# IIoT_Schematic.net
KiCad netlist of a schematic drawn in EAGLE
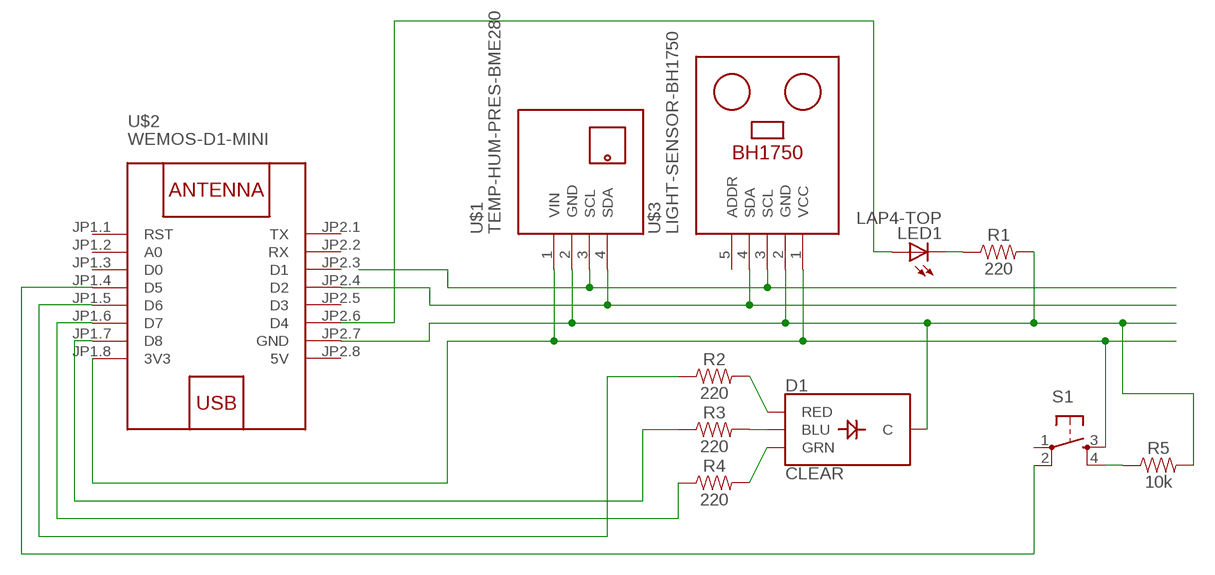
[diagram p0: schematic, sheet 1]

(export (version "E")
  (design (tool "Eeschema 10.0.6"))
  (components
    (comp (ref "D1")
      (value "CLEAR")
      (footprint "eagle-import:LED-RGB-THRU")
      (libsource (lib "eagle-import") (part "LED-RGB-CCCLEAR"))
    )
    (comp (ref "LED1")
      (value "LAP4-TOP")
      (footprint "eagle-import:P47F-TOP")
      (libsource (lib "eagle-import") (part "P4-TOPLA"))
    )
    (comp (ref "R1")
      (value "220")
      (footprint "eagle-import:0603")
      (libsource (lib "eagle-import") (part "220OHM-0603-1/10W-1%"))
    )
    (comp (ref "R2")
      (value "220")
      (footprint "eagle-import:0603")
      (libsource (lib "eagle-import") (part "220OHM-0603-1/10W-1%"))
    )
    (comp (ref "R3")
      (value "220")
      (footprint "eagle-import:0603")
      (libsource (lib "eagle-import") (part "220OHM-0603-1/10W-1%"))
    )
    (comp (ref "R4")
      (value "220")
      (footprint "eagle-import:0603")
      (libsource (lib "eagle-import") (part "220OHM-0603-1/10W-1%"))
    )
    (comp (ref "R5")
      (value "10k")
      (footprint "eagle-import:AXIAL-0.3")
      (libsource (lib "eagle-import") (part "10KOHM-HORIZ-1/4W-1%"))
    )
    (comp (ref "S1")
      (value "TAC_SWITCHPTH")
      (footprint "eagle-import:TACTILE-PTH")
      (libsource (lib "eagle-import") (part "TAC_SWITCHPTH"))
    )
    (comp (ref "U$1")
      (value "TEMP-HUM-PRES-BME280")
      (footprint "eagle-import:TEMP-HUM-PRES-BME280")
      (libsource (lib "eagle-import") (part "TEMP-HUM-PRES-BME280"))
    )
    (comp (ref "U$2")
      (value "WEMOS-D1-MINI")
      (footprint "eagle-import:WEMOS-D1-MINI")
      (libsource (lib "eagle-import") (part "WEMOS-D1-MINI"))
    )
    (comp (ref "U$3")
      (value "LIGHT-SENSOR-BH1750")
      (footprint "eagle-import:LIGHT-SENSOR-BH1750")
      (libsource (lib "eagle-import") (part "LIGHT-SENSOR-BH1750"))
    )
  )
  (nets
    (net (code "1") (name "/5V") (class "Default")
      (node (ref "U$2") (pin "JP2.8") (pinfunction "5V_JP2.8") (pintype "power_in"))
    )
    (net (code "2") (name "Net-(D1-BLU)") (class "Default")
      (node (ref "D1") (pin "4") (pinfunction "BLU_4") (pintype "bidirectional"))
      (node (ref "R3") (pin "2") (pinfunction "2_2") (pintype "passive"))
    )
    (net (code "3") (name "Net-(D1-C)") (class "Default")
      (node (ref "D1") (pin "2") (pinfunction "C_2") (pintype "bidirectional"))
      (node (ref "R1") (pin "2") (pinfunction "2_2") (pintype "passive"))
      (node (ref "R5") (pin "P$2") (pinfunction "2_P$2") (pintype "passive"))
      (node (ref "U$1") (pin "2") (pinfunction "GND_2") (pintype "power_in"))
      (node (ref "U$2") (pin "JP2.7") (pinfunction "GND_JP2.7") (pintype "power_in"))
      (node (ref "U$3") (pin "2") (pinfunction "GND_2") (pintype "power_in"))
    )
    (net (code "4") (name "Net-(D1-GRN)") (class "Default")
      (node (ref "D1") (pin "3") (pinfunction "GRN_3") (pintype "bidirectional"))
      (node (ref "R4") (pin "2") (pinfunction "2_2") (pintype "passive"))
    )
    (net (code "5") (name "Net-(D1-RED)") (class "Default")
      (node (ref "D1") (pin "1") (pinfunction "RED_1") (pintype "bidirectional"))
      (node (ref "R2") (pin "2") (pinfunction "2_2") (pintype "passive"))
    )
    (net (code "6") (name "Net-(LED1-PadC)") (class "Default")
      (node (ref "LED1") (pin "C") (pinfunction "C_C") (pintype "passive"))
      (node (ref "R1") (pin "1") (pinfunction "1_1") (pintype "passive"))
    )
    (net (code "7") (name "Net-(R5-1)") (class "Default")
      (node (ref "R5") (pin "P$1") (pinfunction "1_P$1") (pintype "passive"))
      (node (ref "S1") (pin "4") (pinfunction "4_4") (pintype "passive"))
    )
    (net (code "8") (name "Net-(U$1-SCL)") (class "Default")
      (node (ref "U$1") (pin "3") (pinfunction "SCL_3") (pintype "bidirectional"))
      (node (ref "U$3") (pin "3") (pinfunction "SCL_3") (pintype "bidirectional"))
    )
    (net (code "9") (name "Net-(U$1-SDA)") (class "Default")
      (node (ref "U$1") (pin "4") (pinfunction "SDA_4") (pintype "bidirectional"))
      (node (ref "U$2") (pin "JP2.4") (pinfunction "D2_JP2.4") (pintype "bidirectional"))
      (node (ref "U$3") (pin "4") (pinfunction "SDA_4") (pintype "bidirectional"))
    )
    (net (code "10") (name "Net-(U$1-VIN)") (class "Default")
      (node (ref "S1") (pin "3") (pinfunction "3_3") (pintype "passive"))
      (node (ref "U$1") (pin "1") (pinfunction "VIN_1") (pintype "power_in"))
      (node (ref "U$2") (pin "JP1.8") (pinfunction "3V3_JP1.8") (pintype "power_in"))
      (node (ref "U$3") (pin "1") (pinfunction "VCC_1") (pintype "power_in"))
    )
    (net (code "11") (name "Net-(U$2-D4)") (class "Default")
      (node (ref "LED1") (pin "A") (pinfunction "A_A") (pintype "passive"))
      (node (ref "U$2") (pin "JP2.6") (pinfunction "D4_JP2.6") (pintype "bidirectional"))
    )
    (net (code "12") (name "Net-(U$2-D5)") (class "Default")
      (node (ref "S1") (pin "2") (pinfunction "2_2") (pintype "passive"))
      (node (ref "U$2") (pin "JP1.4") (pinfunction "D5_JP1.4") (pintype "bidirectional"))
    )
    (net (code "13") (name "Net-(U$2-D6)") (class "Default")
      (node (ref "R2") (pin "1") (pinfunction "1_1") (pintype "passive"))
      (node (ref "U$2") (pin "JP1.5") (pinfunction "D6_JP1.5") (pintype "bidirectional"))
    )
    (net (code "14") (name "Net-(U$2-D7)") (class "Default")
      (node (ref "R4") (pin "1") (pinfunction "1_1") (pintype "passive"))
      (node (ref "U$2") (pin "JP1.6") (pinfunction "D7_JP1.6") (pintype "bidirectional"))
    )
    (net (code "15") (name "Net-(U$2-D8)") (class "Default")
      (node (ref "R3") (pin "1") (pinfunction "1_1") (pintype "passive"))
      (node (ref "U$2") (pin "JP1.7") (pinfunction "D8_JP1.7") (pintype "bidirectional"))
    )
    (net (code "16") (name "unconnected-(S1-Pad1)") (class "Default")
      (node (ref "S1") (pin "1") (pinfunction "1_1") (pintype "passive"))
    )
    (net (code "17") (name "unconnected-(U$2-A0-PadJP1.2)") (class "Default")
      (node (ref "U$2") (pin "JP1.2") (pinfunction "A0_JP1.2") (pintype "bidirectional"))
    )
    (net (code "18") (name "unconnected-(U$2-D0-PadJP1.3)") (class "Default")
      (node (ref "U$2") (pin "JP1.3") (pinfunction "D0_JP1.3") (pintype "bidirectional"))
    )
    (net (code "19") (name "unconnected-(U$2-D1-PadJP2.3)") (class "Default")
      (node (ref "U$2") (pin "JP2.3") (pinfunction "D1_JP2.3") (pintype "bidirectional"))
    )
    (net (code "20") (name "unconnected-(U$2-D3-PadJP2.5)") (class "Default")
      (node (ref "U$2") (pin "JP2.5") (pinfunction "D3_JP2.5") (pintype "bidirectional"))
    )
    (net (code "21") (name "unconnected-(U$2-RST-PadJP1.1)") (class "Default")
      (node (ref "U$2") (pin "JP1.1") (pinfunction "RST_JP1.1") (pintype "bidirectional"))
    )
    (net (code "22") (name "unconnected-(U$2-RX-PadJP2.2)") (class "Default")
      (node (ref "U$2") (pin "JP2.2") (pinfunction "RX_JP2.2") (pintype "bidirectional"))
    )
    (net (code "23") (name "unconnected-(U$2-TX-PadJP2.1)") (class "Default")
      (node (ref "U$2") (pin "JP2.1") (pinfunction "TX_JP2.1") (pintype "bidirectional"))
    )
    (net (code "24") (name "unconnected-(U$3-ADDR-Pad5)") (class "Default")
      (node (ref "U$3") (pin "5") (pinfunction "ADDR_5") (pintype "bidirectional"))
    )
  )
)
